# Support_GATEWAY.net
KiCad netlist of a schematic drawn in Altium Designer
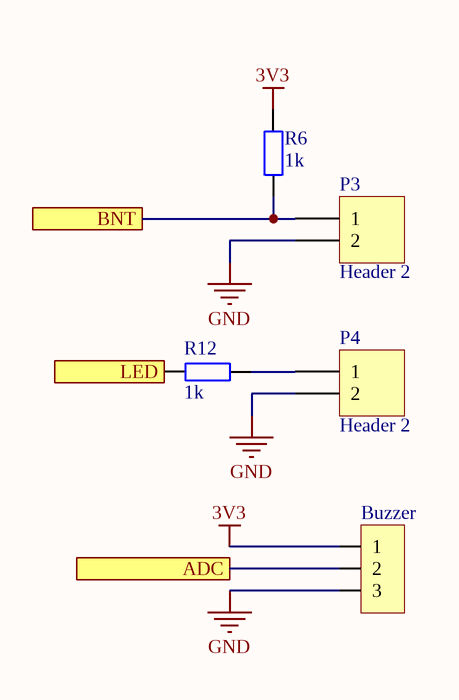
[diagram p0: Support_GATEWAY.SchDoc]

(export (version "E")
  (design (tool "Eeschema 10.0.6"))
  (components
    (comp (ref "JP3")
      (value "Buzzer")
      (footprint "JP3")
      (description "Cắm")
      (libsource (lib "Jump") (part "JP 1x3 2.54 Cai Thang"))
    )
    (comp (ref "P3")
      (value "Header 2")
      (footprint "Header 2")
      (description "Header, 2-Pin")
      (fields (field (name "PUBLISHER") "Altium Limited"))
      (libsource (lib "hphonglib") (part "Header 2"))
    )
    (comp (ref "P4")
      (value "Header 2")
      (footprint "Header 2")
      (description "Header, 2-Pin")
      (fields (field (name "PUBLISHER") "Altium Limited"))
      (libsource (lib "hphonglib") (part "Header 2"))
    )
    (comp (ref "R6")
      (value "1k")
      (footprint "RES-SMD-0603")
      (description "Resistor SMD")
      (fields
        (field (name "MANUFACTURER") "Generic Components")
        (field (name "PUBLISHER") "Altium Hobart Technology Centre")
      )
      (libsource (lib "My Library") (part "Resistor - SMD"))
    )
    (comp (ref "R12")
      (value "1k")
      (footprint "RES-SMD-0603")
      (description "Resistor SMD")
      (fields
        (field (name "MANUFACTURER") "Generic Components")
        (field (name "PUBLISHER") "Altium Hobart Technology Centre")
      )
      (libsource (lib "My Library") (part "Resistor - SMD"))
    )
  )
  (nets
    (net (code "1") (name "/ADC") (class "Default")
      (node (ref "JP3") (pin "2") (pinfunction "2_2") (pintype "passive"))
    )
    (net (code "2") (name "/BNT") (class "Default")
      (node (ref "P3") (pin "1") (pinfunction "1_1") (pintype "passive"))
      (node (ref "R6") (pin "1") (pinfunction "1_1") (pintype "passive"))
    )
    (net (code "3") (name "/LED") (class "Default")
      (node (ref "R12") (pin "1") (pinfunction "1_1") (pintype "passive"))
    )
    (net (code "4") (name "3V3") (class "Default")
      (node (ref "JP3") (pin "1") (pinfunction "1_1") (pintype "passive"))
      (node (ref "R6") (pin "2") (pinfunction "2_2") (pintype "passive"))
    )
    (net (code "5") (name "GND") (class "Default")
      (node (ref "JP3") (pin "3") (pinfunction "3_3") (pintype "passive"))
      (node (ref "P3") (pin "2") (pinfunction "2_2") (pintype "passive"))
      (node (ref "P4") (pin "2") (pinfunction "2_2") (pintype "passive"))
    )
    (net (code "6") (name "Net-(P4-Pad1)") (class "Default")
      (node (ref "P4") (pin "1") (pinfunction "1_1") (pintype "passive"))
      (node (ref "R12") (pin "2") (pinfunction "2_2") (pintype "passive"))
    )
  )
)
